# DC_DC_Converter.net
KiCad netlist of a schematic drawn in Altium Designer
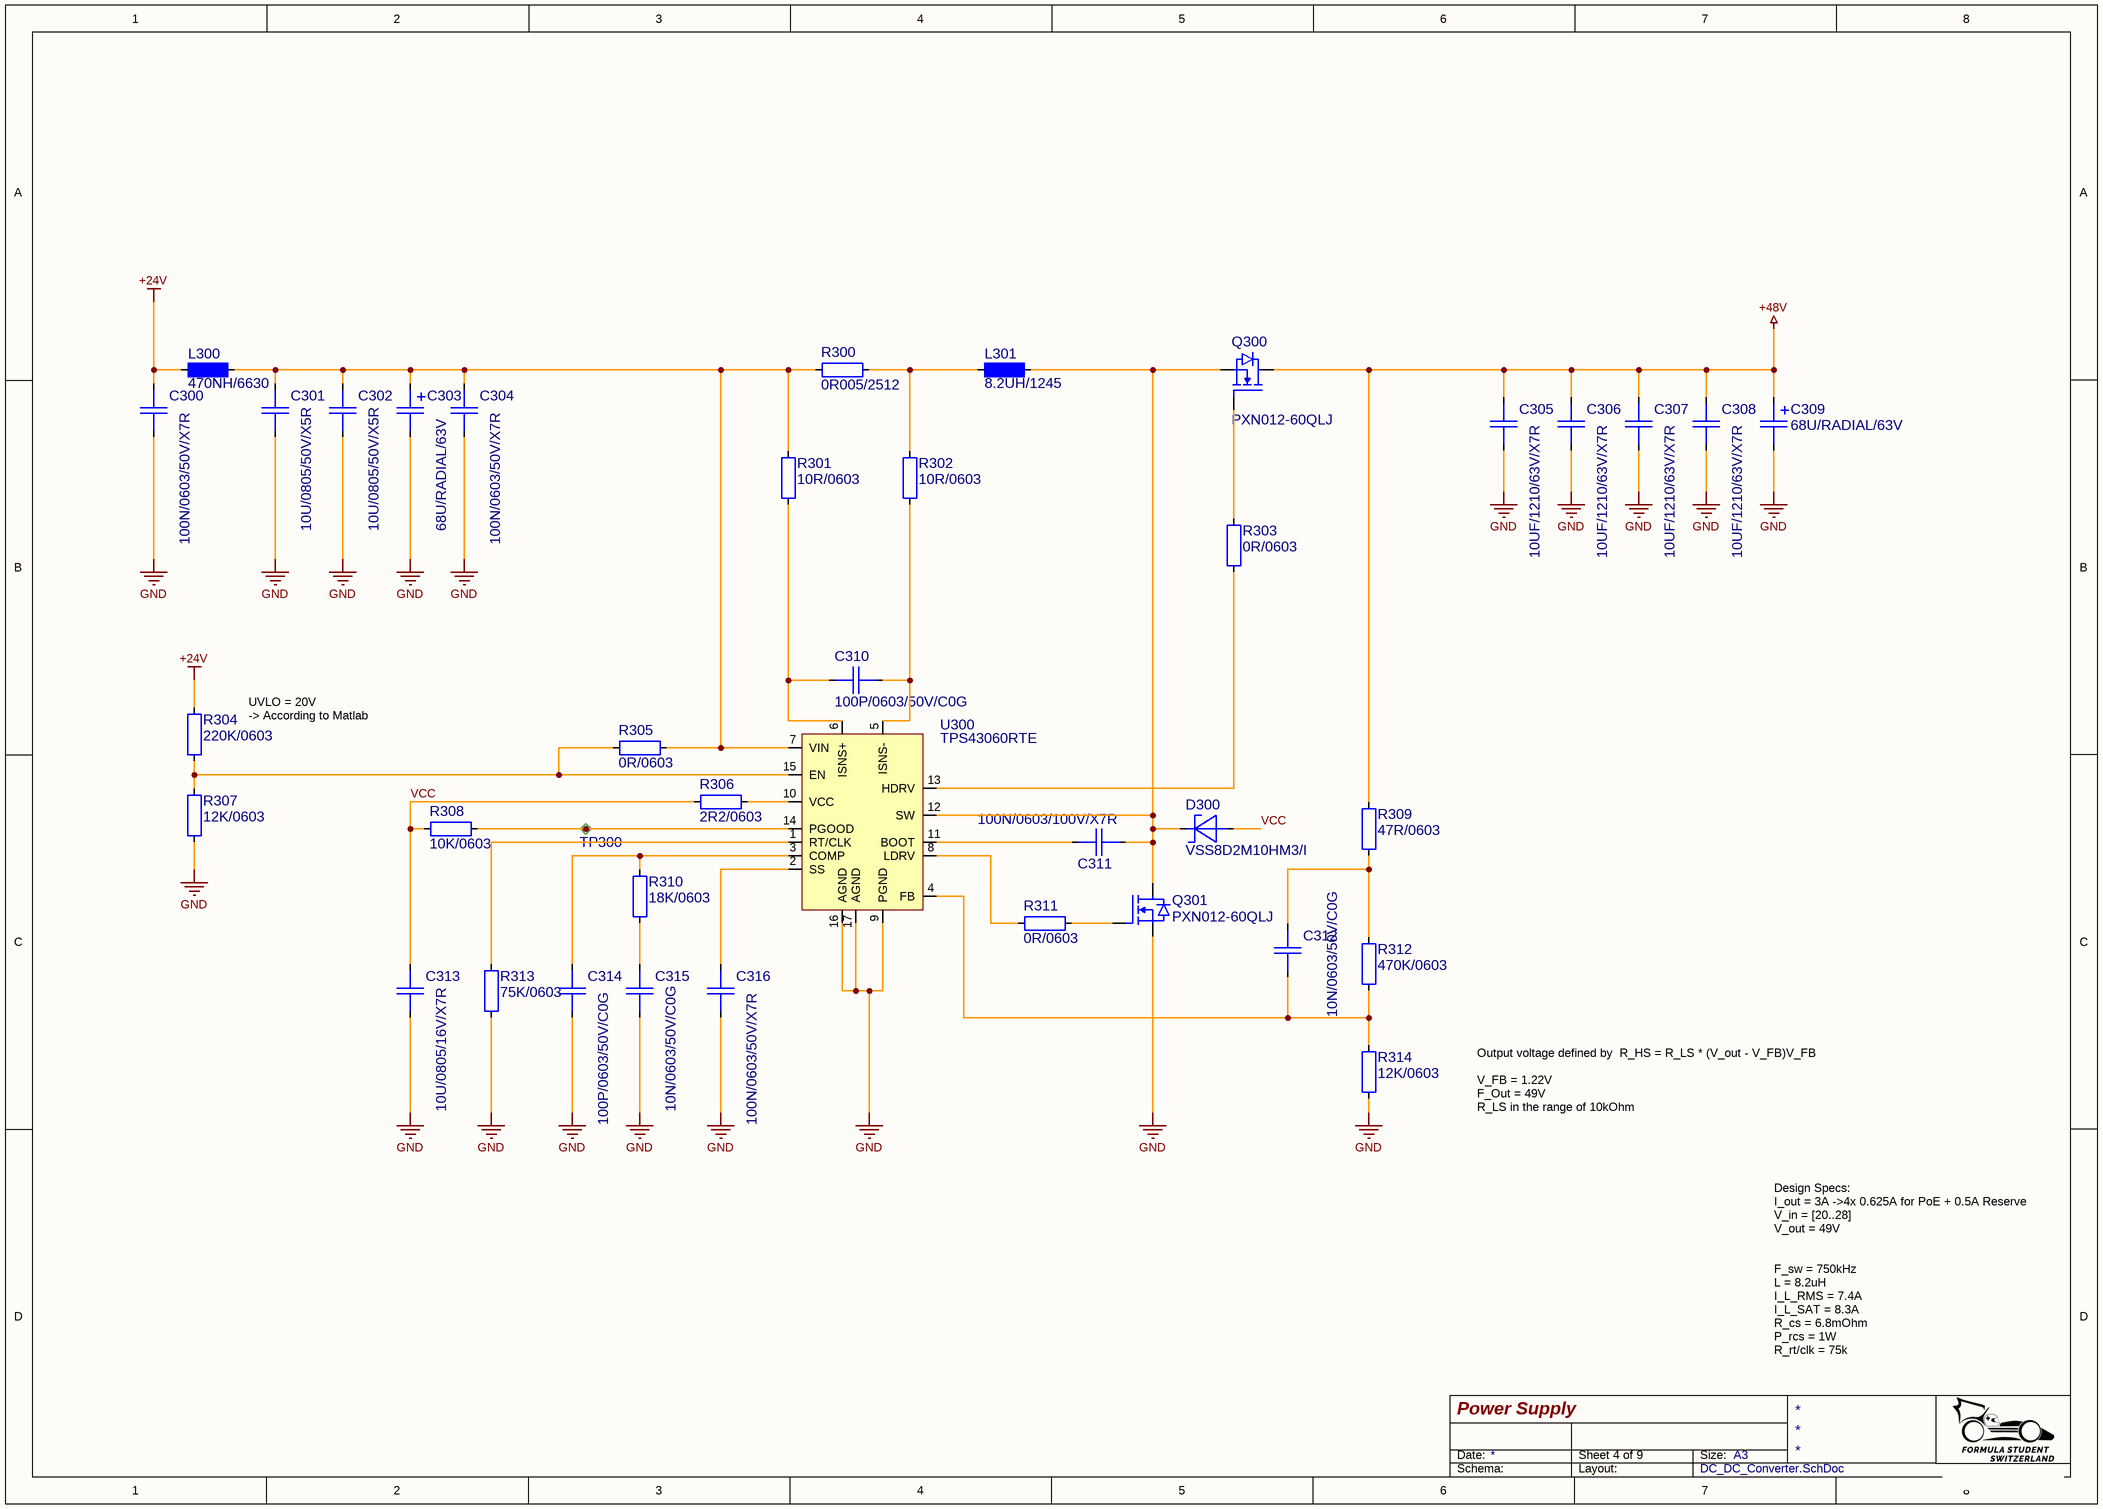
[diagram p0: DC_DC_Converter.SchDoc]

(export (version "E")
  (design (tool "Eeschema 10.0.6"))
  (components
    (comp (ref "C300")
      (value "100N/0603/50V/X7R")
      (footprint "CAP0603_X7R")
      (description "CAP SM 0603 100nF 50V X7R")
      (fields (field (name "MANUFACTURER") "GENERIC"))
      (libsource (lib "daniw_altium_lib") (part "C"))
    )
    (comp (ref "C301")
      (value "10U/0805/50V/X5R")
      (footprint "CAP0805_X7R")
      (description "CAP SM 0805 10uF 50V X5R")
      (fields (field (name "MANUFACTURER") "GENERIC"))
      (libsource (lib "daniw_altium_lib") (part "C"))
    )
    (comp (ref "C302")
      (value "10U/0805/50V/X5R")
      (footprint "CAP0805_X7R")
      (description "CAP SM 0805 10uF 50V X5R")
      (fields (field (name "MANUFACTURER") "GENERIC"))
      (libsource (lib "daniw_altium_lib") (part "C"))
    )
    (comp (ref "C303")
      (value "68U/RADIAL/63V")
      (footprint "CAP350P80X130")
      (description "CAP THT 8C130 68UF ELKO 63V")
      (fields (field (name "MANUFACTURER") "GENERIC"))
      (libsource (lib "daniw_altium_lib") (part "C_ELEC"))
    )
    (comp (ref "C304")
      (value "100N/0603/50V/X7R")
      (footprint "CAP0603_X7R")
      (description "CAP SM 0603 100nF 50V X7R")
      (fields (field (name "MANUFACTURER") "GENERIC"))
      (libsource (lib "daniw_altium_lib") (part "C"))
    )
    (comp (ref "C305")
      (value "10UF/1210/63V/X7R")
      (footprint "CAP1210_X7R")
      (description "CAP SM 1210 10uF 63V X7R")
      (fields (field (name "MANUFACTURER") "GENERIC"))
      (libsource (lib "daniw_altium_lib") (part "C"))
    )
    (comp (ref "C306")
      (value "10UF/1210/63V/X7R")
      (footprint "CAP1210_X7R")
      (description "CAP SM 1210 10uF 63V X7R")
      (fields (field (name "MANUFACTURER") "GENERIC"))
      (libsource (lib "daniw_altium_lib") (part "C"))
    )
    (comp (ref "C307")
      (value "10UF/1210/63V/X7R")
      (footprint "CAP1210_X7R")
      (description "CAP SM 1210 10uF 63V X7R")
      (fields (field (name "MANUFACTURER") "GENERIC"))
      (libsource (lib "daniw_altium_lib") (part "C"))
    )
    (comp (ref "C308")
      (value "10UF/1210/63V/X7R")
      (footprint "CAP1210_X7R")
      (description "CAP SM 1210 10uF 63V X7R")
      (fields (field (name "MANUFACTURER") "GENERIC"))
      (libsource (lib "daniw_altium_lib") (part "C"))
    )
    (comp (ref "C309")
      (value "68U/RADIAL/63V")
      (footprint "CAP350P80X130")
      (description "CAP THT 8C130 68UF ELKO 63V")
      (fields (field (name "MANUFACTURER") "GENERIC"))
      (libsource (lib "daniw_altium_lib") (part "C_ELEC"))
    )
    (comp (ref "C310")
      (value "100P/0603/50V/C0G")
      (footprint "CAP0603_C0G")
      (description "CAP SM 0603 100pF 50V C0G")
      (fields (field (name "MANUFACTURER") "GENERIC"))
      (libsource (lib "daniw_altium_lib") (part "C"))
    )
    (comp (ref "C311")
      (value "100N/0603/100V/X7R")
      (footprint "CAP0603_X7R")
      (description "CAP SM 0603 100nF 100V X7R")
      (fields (field (name "MANUFACTURER") "GENERIC"))
      (libsource (lib "daniw_altium_lib") (part "C"))
    )
    (comp (ref "C312")
      (value "10N/0603/50V/C0G")
      (footprint "CAP0603_C0G")
      (description "CAP SM 0603 10nF 50V C0G")
      (fields (field (name "MANUFACTURER") "GENERIC"))
      (libsource (lib "daniw_altium_lib") (part "C"))
    )
    (comp (ref "C313")
      (value "10U/0805/16V/X7R")
      (footprint "CAP0805_X7R")
      (description "CAP SM 0805 10uF 16V X7R")
      (fields (field (name "MANUFACTURER") "GENERIC"))
      (libsource (lib "daniw_altium_lib") (part "C"))
    )
    (comp (ref "C314")
      (value "100P/0603/50V/C0G")
      (footprint "CAP0603_C0G")
      (description "CAP SM 0603 100pF 50V C0G")
      (fields (field (name "MANUFACTURER") "GENERIC"))
      (libsource (lib "daniw_altium_lib") (part "C"))
    )
    (comp (ref "C315")
      (value "10N/0603/50V/C0G")
      (footprint "CAP0603_C0G")
      (description "CAP SM 0603 10nF 50V C0G")
      (fields (field (name "MANUFACTURER") "GENERIC"))
      (libsource (lib "daniw_altium_lib") (part "C"))
    )
    (comp (ref "C316")
      (value "100N/0603/50V/X7R")
      (footprint "CAP0603_X7R")
      (description "CAP SM 0603 100nF 50V X7R")
      (fields (field (name "MANUFACTURER") "GENERIC"))
      (libsource (lib "daniw_altium_lib") (part "C"))
    )
    (comp (ref "D300")
      (value "VSS8D2M10HM3/I")
      (footprint "SOD4026X100")
      (description "100V 560mV@2A 2A DO-221AD Automotive Schottky Barrier Diode")
      (fields (field (name "MANUFACTURER") "GENERIC"))
      (libsource (lib "daniw_altium_lib") (part "D_Schottky"))
    )
    (comp (ref "L300")
      (value "470NH/6630")
      (footprint "INDM660730X30")
      (description "FIXED IND 470NH 16.5 A 5.5 MOHM SMD")
      (fields (field (name "MANUFACTURER") "GENERIC"))
      (libsource (lib "daniw_altium_lib") (part "L"))
    )
    (comp (ref "L301")
      (value "8.2UH/1245")
      (footprint "INDM126126X47")
      (description "FIXED IND 8.2UH 1.5 A 21.5 MOHM SMD")
      (fields (field (name "MANUFACTURER") "GENERIC"))
      (libsource (lib "daniw_altium_lib") (part "L"))
    )
    (comp (ref "Q300")
      (value "PXN012-60QLJ")
      (footprint "SON065P330X330X075-5-TH245X175")
      (description "N-channel 60 V, 11.5 mOhm, logic level Trench MOSFET in MLPAK33")
      (fields (field (name "MANUFACTURER") "Nexperia USA Inc."))
      (libsource (lib "daniw_altium_lib") (part "MOSFET N"))
    )
    (comp (ref "Q301")
      (value "PXN012-60QLJ")
      (footprint "SON065P330X330X075-5-TH245X175")
      (description "N-channel 60 V, 11.5 mOhm, logic level Trench MOSFET in MLPAK33")
      (fields (field (name "MANUFACTURER") "Nexperia USA Inc."))
      (libsource (lib "daniw_altium_lib") (part "MOSFET N"))
    )
    (comp (ref "R300")
      (value "0R005/2512")
      (footprint "R2512-0.65-WW")
      (description "RES SM 2512 0R005")
      (fields (field (name "MANUFACTURER") "GENERIC"))
      (libsource (lib "daniw_altium_lib") (part "R"))
    )
    (comp (ref "R301")
      (value "10R/0603")
      (footprint "R0603-0.40-WW")
      (description "RES SM 0603 10R")
      (fields (field (name "MANUFACTURER") "GENERIC"))
      (libsource (lib "daniw_altium_lib") (part "R"))
    )
    (comp (ref "R302")
      (value "10R/0603")
      (footprint "R0603-0.40-WW")
      (description "RES SM 0603 10R")
      (fields (field (name "MANUFACTURER") "GENERIC"))
      (libsource (lib "daniw_altium_lib") (part "R"))
    )
    (comp (ref "R303")
      (value "0R/0603")
      (footprint "R0603-0.40-WW")
      (description "RES SM 0603 0R")
      (fields (field (name "MANUFACTURER") "GENERIC"))
      (libsource (lib "daniw_altium_lib") (part "R"))
    )
    (comp (ref "R304")
      (value "220K/0603")
      (footprint "R0603-0.40-WW")
      (description "RES SM 0603 220K")
      (fields (field (name "MANUFACTURER") "GENERIC"))
      (libsource (lib "daniw_altium_lib") (part "R"))
    )
    (comp (ref "R305")
      (value "0R/0603")
      (footprint "R0603-0.40-WW")
      (description "RES SM 0603 0R")
      (fields (field (name "MANUFACTURER") "GENERIC"))
      (libsource (lib "daniw_altium_lib") (part "R"))
    )
    (comp (ref "R306")
      (value "2R2/0603")
      (footprint "R0603-0.40-WW")
      (description "RES SM 0603 2R2")
      (fields (field (name "MANUFACTURER") "GENERIC"))
      (libsource (lib "daniw_altium_lib") (part "R"))
    )
    (comp (ref "R307")
      (value "12K/0603")
      (footprint "R0603-0.40-WW")
      (description "RES SM 0603 12K")
      (fields (field (name "MANUFACTURER") "GENERIC"))
      (libsource (lib "daniw_altium_lib") (part "R"))
    )
    (comp (ref "R308")
      (value "10K/0603")
      (footprint "R0603-0.40-WW")
      (description "RES SM 0603 10K")
      (fields (field (name "MANUFACTURER") "GENERIC"))
      (libsource (lib "daniw_altium_lib") (part "R"))
    )
    (comp (ref "R309")
      (value "47R/0603")
      (footprint "R0603-0.40-WW")
      (description "RES SM 0603 47R")
      (fields (field (name "MANUFACTURER") "GENERIC"))
      (libsource (lib "daniw_altium_lib") (part "R"))
    )
    (comp (ref "R310")
      (value "18K/0603")
      (footprint "R0603-0.40-WW")
      (description "RES SM 0603 18K")
      (fields (field (name "MANUFACTURER") "GENERIC"))
      (libsource (lib "daniw_altium_lib") (part "R"))
    )
    (comp (ref "R311")
      (value "0R/0603")
      (footprint "R0603-0.40-WW")
      (description "RES SM 0603 0R")
      (fields (field (name "MANUFACTURER") "GENERIC"))
      (libsource (lib "daniw_altium_lib") (part "R"))
    )
    (comp (ref "R312")
      (value "470K/0603")
      (footprint "R0603-0.40-WW")
      (description "RES SM 0603 470K")
      (fields (field (name "MANUFACTURER") "GENERIC"))
      (libsource (lib "daniw_altium_lib") (part "R"))
    )
    (comp (ref "R313")
      (value "75K/0603")
      (footprint "R0603-0.40-WW")
      (description "RES SM 0603 75K")
      (fields (field (name "MANUFACTURER") "GENERIC"))
      (libsource (lib "daniw_altium_lib") (part "R"))
    )
    (comp (ref "R314")
      (value "12K/0603")
      (footprint "R0603-0.40-WW")
      (description "RES SM 0603 12K")
      (fields (field (name "MANUFACTURER") "GENERIC"))
      (libsource (lib "daniw_altium_lib") (part "R"))
    )
    (comp (ref "TP300")
      (value "TP_SMD_1")
      (footprint "TP_SMD_1")
      (description "SMD Test Point 1mm")
      (fields (field (name "PART NUMBER") "TP_IL_SMD_1") (field (name "MANUFACTURER") "NONE"))
      (libsource (lib "daniw_altium_lib") (part "Testpoint_inline"))
    )
    (comp (ref "U300")
      (value "TPS43060RTE")
      (footprint "QFN050P300X300X080-16-TH120X80")
      (description "TPS4306x Low Quiescent Current Synchronous Boost DC-DC Controller With Wide VIN Range")
      (fields (field (name "MANUFACTURER") "Texas Instruments"))
      (libsource (lib "daniw_altium_lib") (part "TPS43060RTE"))
    )
  )
  (nets
    (net (code "1") (name "+24V") (class "Default")
      (node (ref "C300") (pin "1") (pinfunction "1_1") (pintype "passive"))
      (node (ref "L300") (pin "1") (pinfunction "1_1") (pintype "passive"))
      (node (ref "R304") (pin "1") (pinfunction "1_1") (pintype "passive"))
    )
    (net (code "2") (name "+48V") (class "Default")
      (node (ref "C305") (pin "1") (pinfunction "1_1") (pintype "passive"))
      (node (ref "C306") (pin "1") (pinfunction "1_1") (pintype "passive"))
      (node (ref "C307") (pin "1") (pinfunction "1_1") (pintype "passive"))
      (node (ref "C308") (pin "1") (pinfunction "1_1") (pintype "passive"))
      (node (ref "C309") (pin "1") (pinfunction "1_1") (pintype "passive"))
      (node (ref "Q300") (pin "D") (pinfunction "DRAIN_D") (pintype "passive"))
      (node (ref "R309") (pin "1") (pinfunction "1_1") (pintype "passive"))
    )
    (net (code "3") (name "/VCC") (class "Default")
      (node (ref "C313") (pin "1") (pinfunction "1_1") (pintype "passive"))
      (node (ref "D300") (pin "2") (pinfunction "2_2") (pintype "passive"))
      (node (ref "R306") (pin "1") (pinfunction "1_1") (pintype "passive"))
      (node (ref "R308") (pin "1") (pinfunction "1_1") (pintype "passive"))
    )
    (net (code "4") (name "GND") (class "Default")
      (node (ref "C300") (pin "2") (pinfunction "2_2") (pintype "passive"))
      (node (ref "C301") (pin "2") (pinfunction "2_2") (pintype "passive"))
      (node (ref "C302") (pin "2") (pinfunction "2_2") (pintype "passive"))
      (node (ref "C303") (pin "2") (pinfunction "2_2") (pintype "passive"))
      (node (ref "C304") (pin "1") (pinfunction "1_1") (pintype "passive"))
      (node (ref "C305") (pin "2") (pinfunction "2_2") (pintype "passive"))
      (node (ref "C306") (pin "2") (pinfunction "2_2") (pintype "passive"))
      (node (ref "C307") (pin "2") (pinfunction "2_2") (pintype "passive"))
      (node (ref "C308") (pin "2") (pinfunction "2_2") (pintype "passive"))
      (node (ref "C309") (pin "2") (pinfunction "2_2") (pintype "passive"))
      (node (ref "C313") (pin "2") (pinfunction "2_2") (pintype "passive"))
      (node (ref "C314") (pin "2") (pinfunction "2_2") (pintype "passive"))
      (node (ref "C315") (pin "2") (pinfunction "2_2") (pintype "passive"))
      (node (ref "C316") (pin "2") (pinfunction "2_2") (pintype "passive"))
      (node (ref "Q301") (pin "S") (pinfunction "SOURCE_S") (pintype "passive"))
      (node (ref "R307") (pin "2") (pinfunction "2_2") (pintype "passive"))
      (node (ref "R313") (pin "2") (pinfunction "2_2") (pintype "passive"))
      (node (ref "R314") (pin "2") (pinfunction "2_2") (pintype "passive"))
      (node (ref "U300") (pin "16") (pinfunction "AGND_16") (pintype "passive"))
      (node (ref "U300") (pin "17") (pinfunction "AGND_17") (pintype "passive"))
      (node (ref "U300") (pin "9") (pinfunction "PGND_9") (pintype "passive"))
    )
    (net (code "5") (name "Net-(C312-Pad1)") (class "Default")
      (node (ref "C312") (pin "1") (pinfunction "1_1") (pintype "passive"))
      (node (ref "R309") (pin "2") (pinfunction "2_2") (pintype "passive"))
      (node (ref "R312") (pin "1") (pinfunction "1_1") (pintype "passive"))
    )
    (net (code "6") (name "Net-(C315-Pad1)") (class "Default")
      (node (ref "C315") (pin "1") (pinfunction "1_1") (pintype "passive"))
      (node (ref "R310") (pin "2") (pinfunction "2_2") (pintype "passive"))
    )
    (net (code "7") (name "Net-(L301-Pad1)") (class "Default")
      (node (ref "L301") (pin "1") (pinfunction "1_1") (pintype "passive"))
      (node (ref "R300") (pin "2") (pinfunction "2_2") (pintype "passive"))
      (node (ref "R302") (pin "1") (pinfunction "1_1") (pintype "passive"))
    )
    (net (code "8") (name "Net-(Q300-GATE)") (class "Default")
      (node (ref "Q300") (pin "G") (pinfunction "GATE_G") (pintype "passive"))
      (node (ref "R303") (pin "2") (pinfunction "2_2") (pintype "passive"))
    )
    (net (code "9") (name "Net-(Q300-SOURCE)") (class "Default")
      (node (ref "C311") (pin "2") (pinfunction "2_2") (pintype "passive"))
      (node (ref "D300") (pin "1") (pinfunction "1_1") (pintype "passive"))
      (node (ref "L301") (pin "2") (pinfunction "2_2") (pintype "passive"))
      (node (ref "Q300") (pin "S") (pinfunction "SOURCE_S") (pintype "passive"))
      (node (ref "Q301") (pin "D") (pinfunction "DRAIN_D") (pintype "passive"))
      (node (ref "U300") (pin "12") (pinfunction "SW_12") (pintype "passive"))
    )
    (net (code "10") (name "Net-(Q301-GATE)") (class "Default")
      (node (ref "Q301") (pin "G") (pinfunction "GATE_G") (pintype "passive"))
      (node (ref "R311") (pin "2") (pinfunction "2_2") (pintype "passive"))
    )
    (net (code "11") (name "Net-(U300-BOOT)") (class "Default")
      (node (ref "C311") (pin "1") (pinfunction "1_1") (pintype "passive"))
      (node (ref "U300") (pin "11") (pinfunction "BOOT_11") (pintype "passive"))
    )
    (net (code "12") (name "Net-(U300-COMP)") (class "Default")
      (node (ref "C314") (pin "1") (pinfunction "1_1") (pintype "passive"))
      (node (ref "R310") (pin "1") (pinfunction "1_1") (pintype "passive"))
      (node (ref "U300") (pin "3") (pinfunction "COMP_3") (pintype "passive"))
    )
    (net (code "13") (name "Net-(U300-EN)") (class "Default")
      (node (ref "R304") (pin "2") (pinfunction "2_2") (pintype "passive"))
      (node (ref "R305") (pin "1") (pinfunction "1_1") (pintype "passive"))
      (node (ref "R307") (pin "1") (pinfunction "1_1") (pintype "passive"))
      (node (ref "U300") (pin "15") (pinfunction "EN_15") (pintype "passive"))
    )
    (net (code "14") (name "Net-(U300-FB)") (class "Default")
      (node (ref "C312") (pin "2") (pinfunction "2_2") (pintype "passive"))
      (node (ref "R312") (pin "2") (pinfunction "2_2") (pintype "passive"))
      (node (ref "R314") (pin "1") (pinfunction "1_1") (pintype "passive"))
      (node (ref "U300") (pin "4") (pinfunction "FB_4") (pintype "passive"))
    )
    (net (code "15") (name "Net-(U300-HDRV)") (class "Default")
      (node (ref "R303") (pin "1") (pinfunction "1_1") (pintype "passive"))
      (node (ref "U300") (pin "13") (pinfunction "HDRV_13") (pintype "passive"))
    )
    (net (code "16") (name "Net-(U300-ISNS+)") (class "Default")
      (node (ref "C310") (pin "1") (pinfunction "1_1") (pintype "passive"))
      (node (ref "R301") (pin "2") (pinfunction "2_2") (pintype "passive"))
      (node (ref "U300") (pin "6") (pinfunction "ISNS+_6") (pintype "passive"))
    )
    (net (code "17") (name "Net-(U300-ISNS-)") (class "Default")
      (node (ref "C310") (pin "2") (pinfunction "2_2") (pintype "passive"))
      (node (ref "R302") (pin "2") (pinfunction "2_2") (pintype "passive"))
      (node (ref "U300") (pin "5") (pinfunction "ISNS-_5") (pintype "passive"))
    )
    (net (code "18") (name "Net-(U300-LDRV)") (class "Default")
      (node (ref "R311") (pin "1") (pinfunction "1_1") (pintype "passive"))
      (node (ref "U300") (pin "8") (pinfunction "LDRV_8") (pintype "passive"))
    )
    (net (code "19") (name "Net-(U300-PGOOD)") (class "Default")
      (node (ref "R308") (pin "2") (pinfunction "2_2") (pintype "passive"))
      (node (ref "TP300") (pin "1") (pinfunction "1_1") (pintype "passive"))
      (node (ref "U300") (pin "14") (pinfunction "PGOOD_14") (pintype "passive"))
    )
    (net (code "20") (name "Net-(U300-RT{slash}CLK)") (class "Default")
      (node (ref "R313") (pin "1") (pinfunction "1_1") (pintype "passive"))
      (node (ref "U300") (pin "1") (pinfunction "RT/CLK_1") (pintype "passive"))
    )
    (net (code "21") (name "Net-(U300-SS)") (class "Default")
      (node (ref "C316") (pin "1") (pinfunction "1_1") (pintype "passive"))
      (node (ref "U300") (pin "2") (pinfunction "SS_2") (pintype "passive"))
    )
    (net (code "22") (name "Net-(U300-VCC)") (class "Default")
      (node (ref "R306") (pin "2") (pinfunction "2_2") (pintype "passive"))
      (node (ref "U300") (pin "10") (pinfunction "VCC_10") (pintype "passive"))
    )
    (net (code "23") (name "Net-(U300-VIN)") (class "Default")
      (node (ref "C301") (pin "1") (pinfunction "1_1") (pintype "passive"))
      (node (ref "C302") (pin "1") (pinfunction "1_1") (pintype "passive"))
      (node (ref "C303") (pin "1") (pinfunction "1_1") (pintype "passive"))
      (node (ref "C304") (pin "2") (pinfunction "2_2") (pintype "passive"))
      (node (ref "L300") (pin "2") (pinfunction "2_2") (pintype "passive"))
      (node (ref "R300") (pin "1") (pinfunction "1_1") (pintype "passive"))
      (node (ref "R301") (pin "1") (pinfunction "1_1") (pintype "passive"))
      (node (ref "R305") (pin "2") (pinfunction "2_2") (pintype "passive"))
      (node (ref "U300") (pin "7") (pinfunction "VIN_7") (pintype "passive"))
    )
  )
)
